# power.net
KiCad netlist of a schematic drawn in Altium Designer
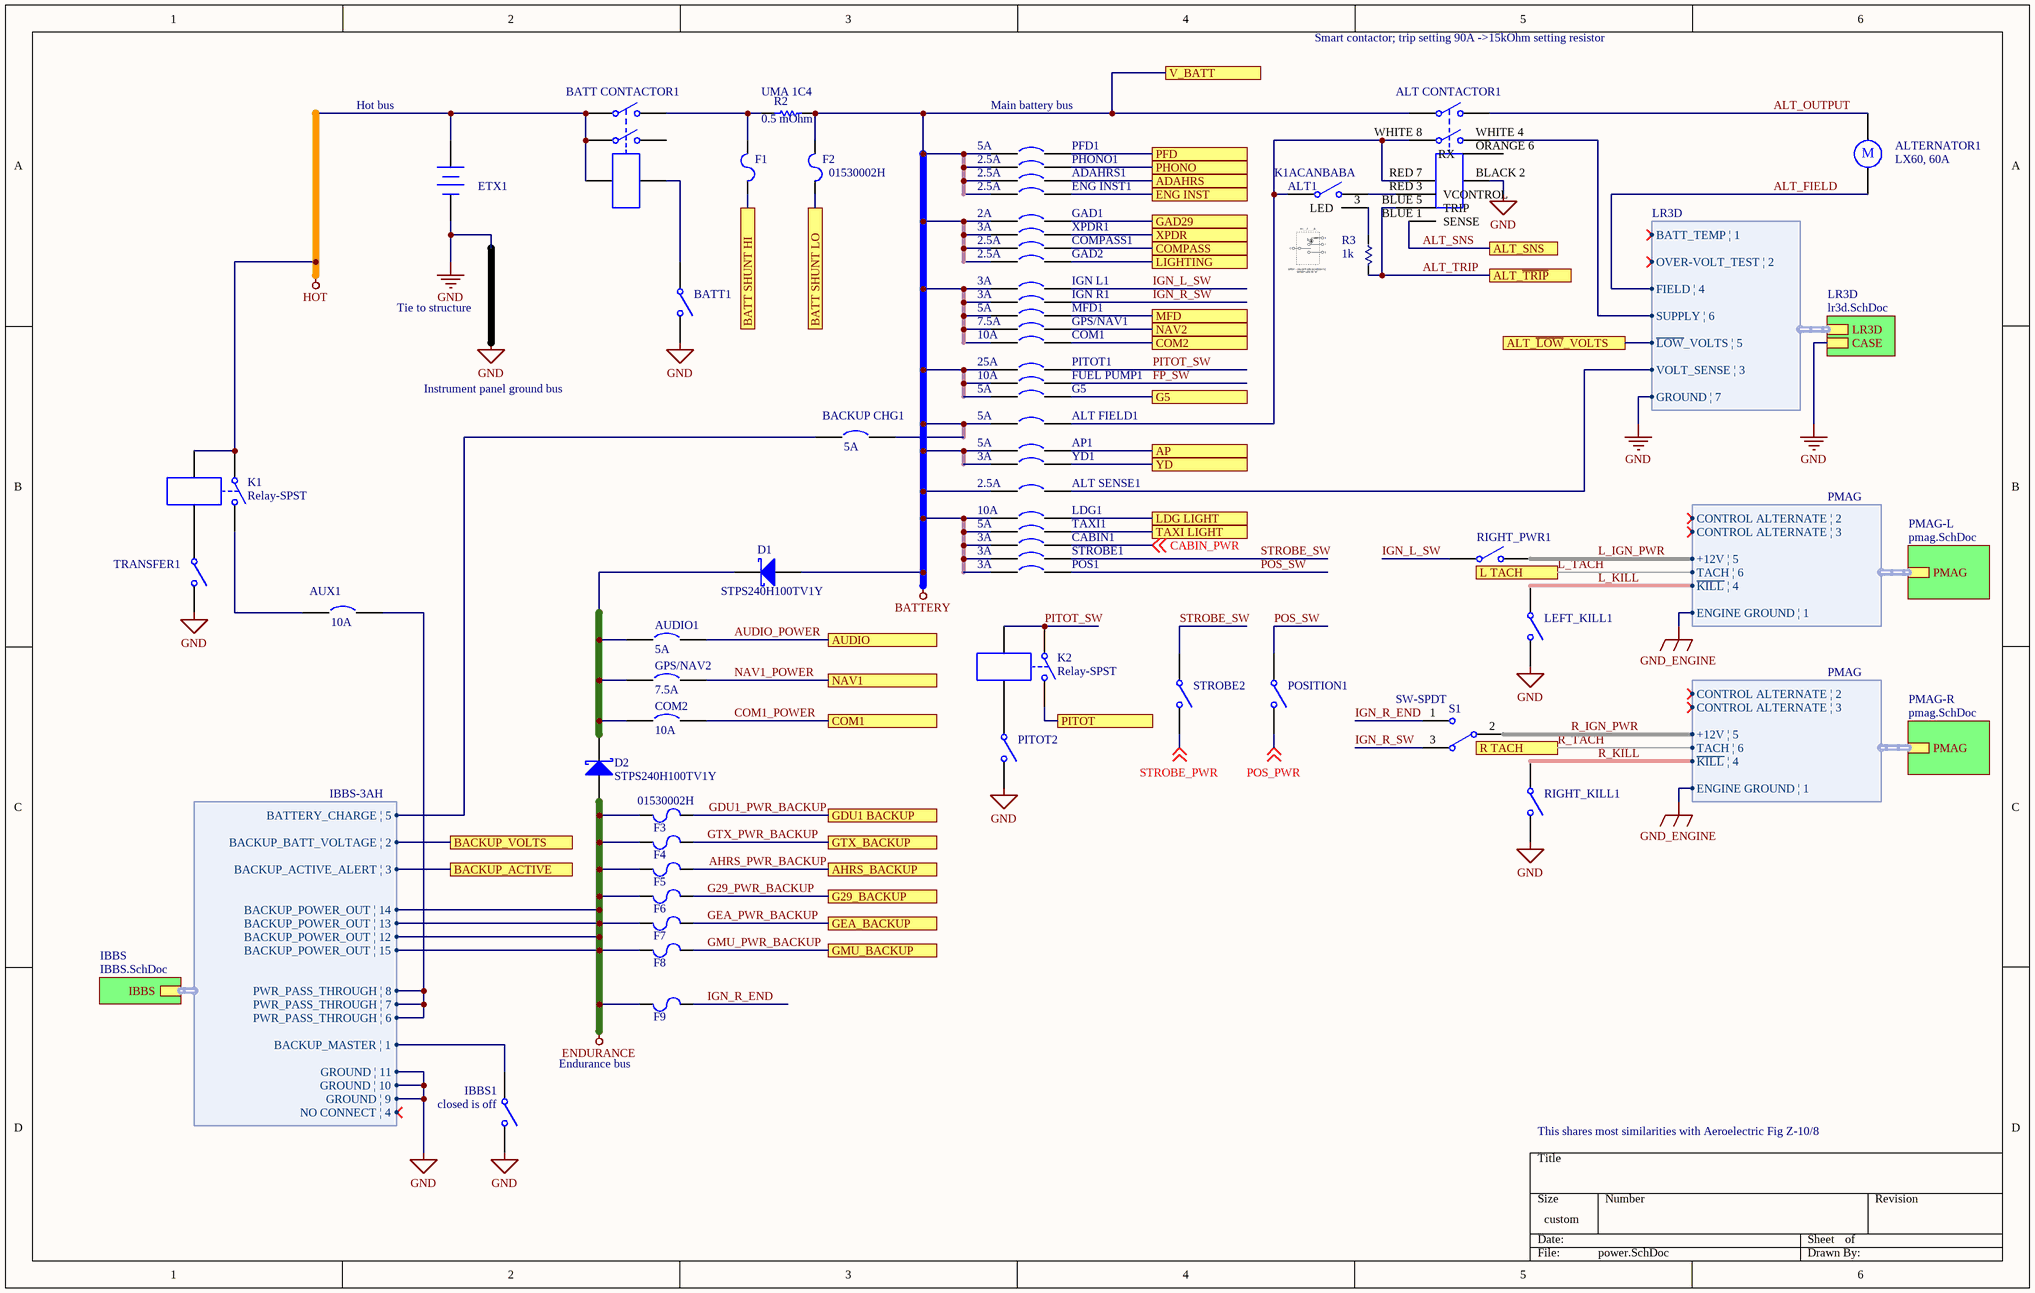
[diagram p0: power.SchDoc]

(export (version "E")
  (design (tool "Eeschema 10.0.6"))
  (components
    (comp (ref "ADAHRS1")
      (value "2.5A")
      (footprint "SPST-2")
      (description "Circuit Breaker")
      (fields (field (name "PUBLISHER") "Altium Limited"))
      (libsource (lib "Miscellaneous Devices") (part "Circuit Breaker"))
    )
    (comp (ref "ALT CONTACTOR1")
      (value "Smart contactor; trip setting 90A ->15kOhm setting resistor")
      (footprint "MODULE6")
      (description "Dual-Pole Single-Throw Relay")
      (fields (field (name "PUBLISHER") "Altium Limited"))
      (libsource (lib "") (part "Relay-DPST_1"))
    )
    (comp (ref "ALT FIELD1")
      (value "5A")
      (footprint "SPST-2")
      (description "Circuit Breaker")
      (fields (field (name "PUBLISHER") "Altium Limited"))
      (libsource (lib "Miscellaneous Devices") (part "Circuit Breaker"))
    )
    (comp (ref "ALT SENSE1")
      (value "2.5A")
      (footprint "SPST-2")
      (description "Circuit Breaker")
      (fields (field (name "PUBLISHER") "Altium Limited"))
      (libsource (lib "Miscellaneous Devices") (part "Circuit Breaker"))
    )
    (comp (ref "ALT1")
      (value "SW-SPST")
      (footprint "SPST-2")
      (description "Single-Pole, Single-Throw Switch")
      (fields (field (name "PUBLISHER") "Altium Limited"))
      (libsource (lib "") (part "SW-SPST_1"))
    )
    (comp (ref "ALTERNATOR1")
      (value "LX60, 60A")
      (footprint "RB5-10.5")
      (description "Motor, General Kind")
      (fields (field (name "PUBLISHER") "Altium Limited"))
      (libsource (lib "Miscellaneous Devices") (part "Motor"))
    )
    (comp (ref "AP1")
      (value "5A")
      (footprint "SPST-2")
      (description "Circuit Breaker")
      (fields (field (name "PUBLISHER") "Altium Limited"))
      (libsource (lib "Miscellaneous Devices") (part "Circuit Breaker"))
    )
    (comp (ref "AUDIO1")
      (value "5A")
      (footprint "SPST-2")
      (description "Circuit Breaker")
      (fields (field (name "PUBLISHER") "Altium Limited"))
      (libsource (lib "Miscellaneous Devices") (part "Circuit Breaker"))
    )
    (comp (ref "AUX1")
      (value "10A")
      (footprint "SPST-2")
      (description "Circuit Breaker")
      (fields (field (name "PUBLISHER") "Altium Limited"))
      (libsource (lib "Miscellaneous Devices") (part "Circuit Breaker"))
    )
    (comp (ref "BACKUP CHG1")
      (value "5A")
      (footprint "SPST-2")
      (description "Circuit Breaker")
      (fields (field (name "PUBLISHER") "Altium Limited"))
      (libsource (lib "Miscellaneous Devices") (part "Circuit Breaker"))
    )
    (comp (ref "BATT CONTACTOR1")
      (value "Relay-DPST")
      (footprint "MODULE6")
      (description "Dual-Pole Single-Throw Relay")
      (fields (field (name "PUBLISHER") "Altium Limited"))
      (libsource (lib "Miscellaneous Devices") (part "Relay-DPST"))
    )
    (comp (ref "BATT1")
      (value "SW-SPST")
      (footprint "SPST-2")
      (description "Single-Pole, Single-Throw Switch")
      (fields (field (name "PUBLISHER") "Altium Limited"))
      (libsource (lib "Miscellaneous Devices") (part "SW-SPST"))
    )
    (comp (ref "CABIN1")
      (value "3A")
      (footprint "SPST-2")
      (description "Circuit Breaker")
      (fields (field (name "PUBLISHER") "Altium Limited"))
      (libsource (lib "Miscellaneous Devices") (part "Circuit Breaker"))
    )
    (comp (ref "COM1")
      (value "10A")
      (footprint "SPST-2")
      (description "Circuit Breaker")
      (fields (field (name "PUBLISHER") "Altium Limited"))
      (libsource (lib "Miscellaneous Devices") (part "Circuit Breaker"))
    )
    (comp (ref "COM2")
      (value "10A")
      (footprint "SPST-2")
      (description "Circuit Breaker")
      (fields (field (name "PUBLISHER") "Altium Limited"))
      (libsource (lib "Miscellaneous Devices") (part "Circuit Breaker"))
    )
    (comp (ref "COMPASS1")
      (value "2.5A")
      (footprint "SPST-2")
      (description "Circuit Breaker")
      (fields (field (name "PUBLISHER") "Altium Limited"))
      (libsource (lib "Miscellaneous Devices") (part "Circuit Breaker"))
    )
    (comp (ref "D1")
      (value "STPS240H100TV1Y")
      (footprint "TO-220AC")
      (description "Schottky Rectifier")
      (fields (field (name "PUBLISHER") "Altium Limited"))
      (libsource (lib "Miscellaneous Devices") (part "Diode 10TQ035"))
    )
    (comp (ref "D2")
      (value "STPS240H100TV1Y")
      (footprint "TO-220AC")
      (description "Schottky Rectifier")
      (fields (field (name "PUBLISHER") "Altium Limited"))
      (libsource (lib "Miscellaneous Devices") (part "Diode 10TQ035"))
    )
    (comp (ref "ENG INST1")
      (value "2.5A")
      (footprint "SPST-2")
      (description "Circuit Breaker")
      (fields (field (name "PUBLISHER") "Altium Limited"))
      (libsource (lib "Miscellaneous Devices") (part "Circuit Breaker"))
    )
    (comp (ref "ETX1")
      (value "Battery")
      (footprint "BAT-2")
      (description "Multicell Battery")
      (fields (field (name "PUBLISHER") "Altium Limited"))
      (libsource (lib "Miscellaneous Devices") (part "Battery"))
    )
    (comp (ref "F1") (value "Fuse") (libsource (lib "component-lib") (part "Fuse")))
    (comp (ref "F2") (value "01530002H") (libsource (lib "component-lib") (part "Fuse")))
    (comp (ref "F3") (value "01530002H") (libsource (lib "component-lib") (part "Fuse")))
    (comp (ref "F4") (value "Fuse") (libsource (lib "component-lib") (part "Fuse")))
    (comp (ref "F5") (value "Fuse") (libsource (lib "component-lib") (part "Fuse")))
    (comp (ref "F6") (value "Fuse") (libsource (lib "component-lib") (part "Fuse")))
    (comp (ref "F7") (value "Fuse") (libsource (lib "component-lib") (part "Fuse")))
    (comp (ref "F8") (value "Fuse") (libsource (lib "component-lib") (part "Fuse")))
    (comp (ref "F9") (value "Fuse") (libsource (lib "component-lib") (part "Fuse")))
    (comp (ref "FUEL PUMP1")
      (value "10A")
      (footprint "SPST-2")
      (description "Circuit Breaker")
      (fields (field (name "PUBLISHER") "Altium Limited"))
      (libsource (lib "Miscellaneous Devices") (part "Circuit Breaker"))
    )
    (comp (ref "G5")
      (value "5A")
      (footprint "SPST-2")
      (description "Circuit Breaker")
      (fields (field (name "PUBLISHER") "Altium Limited"))
      (libsource (lib "Miscellaneous Devices") (part "Circuit Breaker"))
    )
    (comp (ref "GAD1")
      (value "2A")
      (footprint "SPST-2")
      (description "Circuit Breaker")
      (fields (field (name "PUBLISHER") "Altium Limited"))
      (libsource (lib "Miscellaneous Devices") (part "Circuit Breaker"))
    )
    (comp (ref "GAD2")
      (value "2.5A")
      (footprint "SPST-2")
      (description "Circuit Breaker")
      (fields (field (name "PUBLISHER") "Altium Limited"))
      (libsource (lib "Miscellaneous Devices") (part "Circuit Breaker"))
    )
    (comp (ref "GPS/NAV1")
      (value "7.5A")
      (footprint "SPST-2")
      (description "Circuit Breaker")
      (fields (field (name "PUBLISHER") "Altium Limited"))
      (libsource (lib "Miscellaneous Devices") (part "Circuit Breaker"))
    )
    (comp (ref "GPS/NAV2")
      (value "7.5A")
      (footprint "SPST-2")
      (description "Circuit Breaker")
      (fields (field (name "PUBLISHER") "Altium Limited"))
      (libsource (lib "Miscellaneous Devices") (part "Circuit Breaker"))
    )
    (comp (ref "IBBS1")
      (value "SW-SPST")
      (footprint "SPST-2")
      (description "Single-Pole, Single-Throw Switch")
      (fields (field (name "PUBLISHER") "Altium Limited"))
      (libsource (lib "Miscellaneous Devices") (part "SW-SPST"))
    )
    (comp (ref "IGN L1")
      (value "3A")
      (footprint "SPST-2")
      (description "Circuit Breaker")
      (fields (field (name "PUBLISHER") "Altium Limited"))
      (libsource (lib "Miscellaneous Devices") (part "Circuit Breaker"))
    )
    (comp (ref "IGN R1")
      (value "3A")
      (footprint "SPST-2")
      (description "Circuit Breaker")
      (fields (field (name "PUBLISHER") "Altium Limited"))
      (libsource (lib "Miscellaneous Devices") (part "Circuit Breaker"))
    )
    (comp (ref "K1")
      (value "Relay-SPST")
      (footprint "MODULE4")
      (description "Single-Pole Single-Throw Relay")
      (fields (field (name "PUBLISHER") "Altium Limited"))
      (libsource (lib "Miscellaneous Devices") (part "Relay-SPST"))
    )
    (comp (ref "K2")
      (value "Relay-SPST")
      (footprint "MODULE4")
      (description "Single-Pole Single-Throw Relay")
      (fields (field (name "PUBLISHER") "Altium Limited"))
      (libsource (lib "Miscellaneous Devices") (part "Relay-SPST"))
    )
    (comp (ref "LDG1")
      (value "10A")
      (footprint "SPST-2")
      (description "Circuit Breaker")
      (fields (field (name "PUBLISHER") "Altium Limited"))
      (libsource (lib "Miscellaneous Devices") (part "Circuit Breaker"))
    )
    (comp (ref "LEFT_KILL1")
      (value "SW-SPST")
      (footprint "SPST-2")
      (description "Single-Pole, Single-Throw Switch")
      (fields (field (name "PUBLISHER") "Altium Limited"))
      (libsource (lib "Miscellaneous Devices") (part "SW-SPST"))
    )
    (comp (ref "MFD1")
      (value "5A")
      (footprint "SPST-2")
      (description "Circuit Breaker")
      (fields (field (name "PUBLISHER") "Altium Limited"))
      (libsource (lib "Miscellaneous Devices") (part "Circuit Breaker"))
    )
    (comp (ref "PFD1")
      (value "5A")
      (footprint "SPST-2")
      (description "Circuit Breaker")
      (fields (field (name "PUBLISHER") "Altium Limited"))
      (libsource (lib "Miscellaneous Devices") (part "Circuit Breaker"))
    )
    (comp (ref "PHONO1")
      (value "2.5A")
      (footprint "SPST-2")
      (description "Circuit Breaker")
      (fields (field (name "PUBLISHER") "Altium Limited"))
      (libsource (lib "Miscellaneous Devices") (part "Circuit Breaker"))
    )
    (comp (ref "PITOT1")
      (value "25A")
      (footprint "SPST-2")
      (description "Circuit Breaker")
      (fields (field (name "PUBLISHER") "Altium Limited"))
      (libsource (lib "Miscellaneous Devices") (part "Circuit Breaker"))
    )
    (comp (ref "PITOT2")
      (value "SW-SPST")
      (footprint "SPST-2")
      (description "Single-Pole, Single-Throw Switch")
      (fields (field (name "PUBLISHER") "Altium Limited"))
      (libsource (lib "Miscellaneous Devices") (part "SW-SPST"))
    )
    (comp (ref "POS1")
      (value "3A")
      (footprint "SPST-2")
      (description "Circuit Breaker")
      (fields (field (name "PUBLISHER") "Altium Limited"))
      (libsource (lib "Miscellaneous Devices") (part "Circuit Breaker"))
    )
    (comp (ref "POSITION1")
      (value "SW-SPST")
      (footprint "SPST-2")
      (description "Single-Pole, Single-Throw Switch")
      (fields (field (name "PUBLISHER") "Altium Limited"))
      (libsource (lib "Miscellaneous Devices") (part "SW-SPST"))
    )
    (comp (ref "R2")
      (value "UMA 1C4")
      (footprint "AXIAL-0.3")
      (description "Resistor")
      (fields (field (name "ALTIUM_VALUE") "0.5 mOhm") (field (name "PUBLISHER") "Altium Limited"))
      (libsource (lib "Miscellaneous Devices") (part "Res1"))
    )
    (comp (ref "R3")
      (value "RN60D1001FRE6")
      (footprint "RESC1608L")
      (fields (field (name "TOLERANCE") "±5%") (field (name "RESISTANCE (OHMS)") "1k"))
      (libsource (lib "resistor") (part "RES_470-0603"))
    )
    (comp (ref "RIGHT_KILL1")
      (value "SW-SPST")
      (footprint "SPST-2")
      (description "Single-Pole, Single-Throw Switch")
      (fields (field (name "PUBLISHER") "Altium Limited"))
      (libsource (lib "Miscellaneous Devices") (part "SW-SPST"))
    )
    (comp (ref "RIGHT_PWR1")
      (value "SW-SPST")
      (footprint "SPST-2")
      (description "Single-Pole, Single-Throw Switch")
      (fields (field (name "PUBLISHER") "Altium Limited"))
      (libsource (lib "Miscellaneous Devices") (part "SW-SPST"))
    )
    (comp (ref "S1")
      (value "SW-SPDT")
      (footprint "TL36WW15050")
      (description "SPDT Subminiature Toggle Switch, Right Angle Mounting, Vertical Actuation")
      (fields (field (name "PUBLISHER") "Altium Limited"))
      (libsource (lib "Miscellaneous Devices") (part "SW-SPDT"))
    )
    (comp (ref "STROBE1")
      (value "3A")
      (footprint "SPST-2")
      (description "Circuit Breaker")
      (fields (field (name "PUBLISHER") "Altium Limited"))
      (libsource (lib "Miscellaneous Devices") (part "Circuit Breaker"))
    )
    (comp (ref "STROBE2")
      (value "SW-SPST")
      (footprint "SPST-2")
      (description "Single-Pole, Single-Throw Switch")
      (fields (field (name "PUBLISHER") "Altium Limited"))
      (libsource (lib "Miscellaneous Devices") (part "SW-SPST"))
    )
    (comp (ref "TAXI1")
      (value "5A")
      (footprint "SPST-2")
      (description "Circuit Breaker")
      (fields (field (name "PUBLISHER") "Altium Limited"))
      (libsource (lib "Miscellaneous Devices") (part "Circuit Breaker"))
    )
    (comp (ref "TRANSFER1")
      (value "SW-SPST")
      (footprint "SPST-2")
      (description "Single-Pole, Single-Throw Switch")
      (fields (field (name "PUBLISHER") "Altium Limited"))
      (libsource (lib "Miscellaneous Devices") (part "SW-SPST"))
    )
    (comp (ref "XPDR1")
      (value "3A")
      (footprint "SPST-2")
      (description "Circuit Breaker")
      (fields (field (name "PUBLISHER") "Altium Limited"))
      (libsource (lib "Miscellaneous Devices") (part "Circuit Breaker"))
    )
    (comp (ref "YD1")
      (value "3A")
      (footprint "SPST-2")
      (description "Circuit Breaker")
      (fields (field (name "PUBLISHER") "Altium Limited"))
      (libsource (lib "Miscellaneous Devices") (part "Circuit Breaker"))
    )
  )
  (nets
    (net (code "4") (name "/ADAHRS") (class "Default")
      (node (ref "ADAHRS1") (pin "2") (pinfunction "2_2") (pintype "passive"))
    )
    (net (code "5") (name "/AHRS_PWR_BACKUP") (class "Default")
      (node (ref "F5") (pin "14") (pinfunction "14_14") (pintype "passive"))
    )
    (net (code "6") (name "/ALT_FIELD") (class "Default")
      (node (ref "ALTERNATOR1") (pin "2") (pinfunction "2_2") (pintype "passive"))
    )
    (net (code "7") (name "/ALT_OUTPUT") (class "Default")
      (node (ref "ALT CONTACTOR1") (pin "2") (pinfunction "2_2") (pintype "passive"))
      (node (ref "ALTERNATOR1") (pin "1") (pinfunction "1_1") (pintype "passive"))
    )
    (net (code "8") (name "/ALT_SNS") (class "Default")
      (node (ref "ALT CONTACTOR1") (pin "BLUE_1") (pinfunction "SENSE_BLUE_1") (pintype "passive"))
    )
    (net (code "9") (name "/ALT_TRIP") (class "Default")
      (node (ref "ALT CONTACTOR1") (pin "BLUE_5") (pinfunction "TRIP_BLUE_5") (pintype "passive"))
      (node (ref "R3") (pin "2") (pintype "passive"))
    )
    (net (code "11") (name "/AP") (class "Default")
      (node (ref "AP1") (pin "2") (pinfunction "2_2") (pintype "passive"))
    )
    (net (code "12") (name "/AUDIO_POWER") (class "Default")
      (node (ref "AUDIO1") (pin "2") (pinfunction "2_2") (pintype "passive"))
    )
    (net (code "14") (name "/BACKUP_MASTER ¦ 1") (class "Default")
      (node (ref "IBBS1") (pin "1") (pinfunction "COMMON_1") (pintype "passive"))
    )
    (net (code "16") (name "/BATT SHUNT HI") (class "Default")
      (node (ref "F1") (pin "14") (pinfunction "14_14") (pintype "passive"))
    )
    (net (code "17") (name "/BATT SHUNT LO") (class "Default")
      (node (ref "F2") (pin "14") (pinfunction "14_14") (pintype "passive"))
    )
    (net (code "18") (name "/BATTERY_CHARGE ¦ 5") (class "Default")
      (node (ref "BACKUP CHG1") (pin "1") (pinfunction "1_1") (pintype "passive"))
    )
    (net (code "19") (name "/COM1_POWER") (class "Default")
      (node (ref "COM2") (pin "2") (pinfunction "2_2") (pintype "passive"))
    )
    (net (code "20") (name "/COM2") (class "Default")
      (node (ref "COM1") (pin "2") (pinfunction "2_2") (pintype "passive"))
    )
    (net (code "21") (name "/COMPASS") (class "Default")
      (node (ref "COMPASS1") (pin "2") (pinfunction "2_2") (pintype "passive"))
    )
    (net (code "22") (name "/ENG INST") (class "Default")
      (node (ref "ENG INST1") (pin "2") (pinfunction "2_2") (pintype "passive"))
    )
    (net (code "23") (name "/FP_SW") (class "Default")
      (node (ref "FUEL PUMP1") (pin "2") (pinfunction "2_2") (pintype "passive"))
    )
    (net (code "24") (name "/G5") (class "Default")
      (node (ref "G5") (pin "2") (pinfunction "2_2") (pintype "passive"))
    )
    (net (code "25") (name "/G29_PWR_BACKUP") (class "Default")
      (node (ref "F6") (pin "14") (pinfunction "14_14") (pintype "passive"))
    )
    (net (code "26") (name "/GAD29") (class "Default")
      (node (ref "GAD1") (pin "2") (pinfunction "2_2") (pintype "passive"))
    )
    (net (code "27") (name "/GDU1_PWR_BACKUP") (class "Default")
      (node (ref "F3") (pin "14") (pinfunction "14_14") (pintype "passive"))
    )
    (net (code "28") (name "/GEA_PWR_BACKUP") (class "Default")
      (node (ref "F7") (pin "14") (pinfunction "14_14") (pintype "passive"))
    )
    (net (code "29") (name "/GMU_PWR_BACKUP") (class "Default")
      (node (ref "F8") (pin "14") (pinfunction "14_14") (pintype "passive"))
    )
    (net (code "30") (name "/GTX_PWR_BACKUP") (class "Default")
      (node (ref "F4") (pin "14") (pinfunction "14_14") (pintype "passive"))
    )
    (net (code "31") (name "/IGN_L_SW") (class "Default")
      (node (ref "IGN L1") (pin "2") (pinfunction "2_2") (pintype "passive"))
      (node (ref "RIGHT_PWR1") (pin "1") (pinfunction "COMMON_1") (pintype "passive"))
    )
    (net (code "32") (name "/IGN_R_END") (class "Default")
      (node (ref "F9") (pin "14") (pinfunction "14_14") (pintype "passive"))
      (node (ref "S1") (pin "1") (pinfunction "1_1") (pintype "passive"))
    )
    (net (code "33") (name "/IGN_R_SW") (class "Default")
      (node (ref "IGN R1") (pin "2") (pinfunction "2_2") (pintype "passive"))
      (node (ref "S1") (pin "3") (pinfunction "3_3") (pintype "passive"))
    )
    (net (code "34") (name "/LDG LIGHT") (class "Default")
      (node (ref "LDG1") (pin "2") (pinfunction "2_2") (pintype "passive"))
    )
    (net (code "35") (name "/LIGHTING") (class "Default")
      (node (ref "GAD2") (pin "2") (pinfunction "2_2") (pintype "passive"))
    )
    (net (code "36") (name "/L_IGN_PWR") (class "Default")
      (node (ref "RIGHT_PWR1") (pin "2") (pinfunction "NO_2") (pintype "passive"))
    )
    (net (code "38") (name "/L_~{KILL}") (class "Default")
      (node (ref "LEFT_KILL1") (pin "1") (pinfunction "COMMON_1") (pintype "passive"))
    )
    (net (code "39") (name "/MFD") (class "Default")
      (node (ref "MFD1") (pin "2") (pinfunction "2_2") (pintype "passive"))
    )
    (net (code "40") (name "/NAV1_POWER") (class "Default")
      (node (ref "GPS/NAV2") (pin "2") (pinfunction "2_2") (pintype "passive"))
    )
    (net (code "41") (name "/NAV2") (class "Default")
      (node (ref "GPS/NAV1") (pin "2") (pinfunction "2_2") (pintype "passive"))
    )
    (net (code "42") (name "/PFD") (class "Default")
      (node (ref "PFD1") (pin "2") (pinfunction "2_2") (pintype "passive"))
    )
    (net (code "43") (name "/PHONO") (class "Default")
      (node (ref "PHONO1") (pin "2") (pinfunction "2_2") (pintype "passive"))
    )
    (net (code "44") (name "/PITOT") (class "Default")
      (node (ref "K2") (pin "2") (pinfunction "2_2") (pintype "passive"))
    )
    (net (code "45") (name "/PITOT_SW") (class "Default")
      (node (ref "K2") (pin "1") (pinfunction "1_1") (pintype "passive"))
      (node (ref "K2") (pin "3") (pinfunction "3_3") (pintype "passive"))
      (node (ref "PITOT1") (pin "2") (pinfunction "2_2") (pintype "passive"))
    )
    (net (code "46") (name "/POS_SW") (class "Default")
      (node (ref "POS1") (pin "2") (pinfunction "2_2") (pintype "passive"))
      (node (ref "POSITION1") (pin "1") (pinfunction "COMMON_1") (pintype "passive"))
    )
    (net (code "47") (name "/PWR_PASS_THROUGH ¦ 6") (class "Default")
      (node (ref "AUX1") (pin "2") (pinfunction "2_2") (pintype "passive"))
    )
    (net (code "48") (name "/R_IGN_PWR") (class "Default")
      (node (ref "S1") (pin "2") (pinfunction "2_2") (pintype "passive"))
    )
    (net (code "50") (name "/R_~{KILL}") (class "Default")
      (node (ref "RIGHT_KILL1") (pin "1") (pinfunction "COMMON_1") (pintype "passive"))
    )
    (net (code "51") (name "/STROBE_SW") (class "Default")
      (node (ref "STROBE1") (pin "2") (pinfunction "2_2") (pintype "passive"))
      (node (ref "STROBE2") (pin "1") (pinfunction "COMMON_1") (pintype "passive"))
    )
    (net (code "52") (name "/SUPPLY ¦ 6") (class "Default")
      (node (ref "ALT CONTACTOR1") (pin "WHITE_4") (pinfunction "4_WHITE_4") (pintype "passive"))
    )
    (net (code "53") (name "/TAXI LIGHT") (class "Default")
      (node (ref "TAXI1") (pin "2") (pinfunction "2_2") (pintype "passive"))
    )
    (net (code "54") (name "/VOLT_SENSE ¦ 3") (class "Default")
      (node (ref "ALT SENSE1") (pin "2") (pinfunction "2_2") (pintype "passive"))
    )
    (net (code "55") (name "/XPDR") (class "Default")
      (node (ref "XPDR1") (pin "2") (pinfunction "2_2") (pintype "passive"))
    )
    (net (code "56") (name "/YD") (class "Default")
      (node (ref "YD1") (pin "2") (pinfunction "2_2") (pintype "passive"))
    )
    (net (code "60") (name "BATTERY") (class "Default")
      (node (ref "ADAHRS1") (pin "1") (pinfunction "1_1") (pintype "passive"))
      (node (ref "ALT CONTACTOR1") (pin "1") (pinfunction "1_1") (pintype "passive"))
      (node (ref "ALT FIELD1") (pin "1") (pinfunction "1_1") (pintype "passive"))
      (node (ref "ALT SENSE1") (pin "1") (pinfunction "1_1") (pintype "passive"))
      (node (ref "AP1") (pin "1") (pinfunction "1_1") (pintype "passive"))
      (node (ref "BACKUP CHG1") (pin "2") (pinfunction "2_2") (pintype "passive"))
      (node (ref "CABIN1") (pin "1") (pinfunction "1_1") (pintype "passive"))
      (node (ref "COM1") (pin "1") (pinfunction "1_1") (pintype "passive"))
      (node (ref "COMPASS1") (pin "1") (pinfunction "1_1") (pintype "passive"))
      (node (ref "D1") (pin "3") (pinfunction "A_3") (pintype "passive"))
      (node (ref "ENG INST1") (pin "1") (pinfunction "1_1") (pintype "passive"))
      (node (ref "F2") (pin "13") (pinfunction "13_13") (pintype "passive"))
      (node (ref "FUEL PUMP1") (pin "1") (pinfunction "1_1") (pintype "passive"))
      (node (ref "G5") (pin "1") (pinfunction "1_1") (pintype "passive"))
      (node (ref "GAD1") (pin "1") (pinfunction "1_1") (pintype "passive"))
      (node (ref "GAD2") (pin "1") (pinfunction "1_1") (pintype "passive"))
      (node (ref "GPS/NAV1") (pin "1") (pinfunction "1_1") (pintype "passive"))
      (node (ref "IGN L1") (pin "1") (pinfunction "1_1") (pintype "passive"))
      (node (ref "IGN R1") (pin "1") (pinfunction "1_1") (pintype "passive"))
      (node (ref "LDG1") (pin "1") (pinfunction "1_1") (pintype "passive"))
      (node (ref "MFD1") (pin "1") (pinfunction "1_1") (pintype "passive"))
      (node (ref "PFD1") (pin "1") (pinfunction "1_1") (pintype "passive"))
      (node (ref "PHONO1") (pin "1") (pinfunction "1_1") (pintype "passive"))
      (node (ref "PITOT1") (pin "1") (pinfunction "1_1") (pintype "passive"))
      (node (ref "POS1") (pin "1") (pinfunction "1_1") (pintype "passive"))
      (node (ref "R2") (pin "2") (pinfunction "2_2") (pintype "passive"))
      (node (ref "STROBE1") (pin "1") (pinfunction "1_1") (pintype "passive"))
      (node (ref "TAXI1") (pin "1") (pinfunction "1_1") (pintype "passive"))
      (node (ref "XPDR1") (pin "1") (pinfunction "1_1") (pintype "passive"))
      (node (ref "YD1") (pin "1") (pinfunction "1_1") (pintype "passive"))
    )
    (net (code "61") (name "CABIN_PWR") (class "Default")
      (node (ref "CABIN1") (pin "2") (pinfunction "2_2") (pintype "passive"))
    )
    (net (code "62") (name "ENDURANCE") (class "Default")
      (node (ref "D2") (pin "3") (pinfunction "A_3") (pintype "passive"))
      (node (ref "F3") (pin "13") (pinfunction "13_13") (pintype "passive"))
      (node (ref "F4") (pin "13") (pinfunction "13_13") (pintype "passive"))
      (node (ref "F5") (pin "13") (pinfunction "13_13") (pintype "passive"))
      (node (ref "F6") (pin "13") (pinfunction "13_13") (pintype "passive"))
      (node (ref "F7") (pin "13") (pinfunction "13_13") (pintype "passive"))
      (node (ref "F8") (pin "13") (pinfunction "13_13") (pintype "passive"))
      (node (ref "F9") (pin "13") (pinfunction "13_13") (pintype "passive"))
    )
    (net (code "63") (name "GND") (class "Default")
      (node (ref "ALT CONTACTOR1") (pin "BLACK_2") (pinfunction "6_BLACK_2") (pintype "passive"))
      (node (ref "BATT1") (pin "2") (pinfunction "NO_2") (pintype "passive"))
      (node (ref "ETX1") (pin "2") (pinfunction "-_2") (pintype "passive"))
      (node (ref "IBBS1") (pin "2") (pinfunction "NO_2") (pintype "passive"))
      (node (ref "LEFT_KILL1") (pin "2") (pinfunction "NO_2") (pintype "passive"))
      (node (ref "PITOT2") (pin "2") (pinfunction "NO_2") (pintype "passive"))
      (node (ref "RIGHT_KILL1") (pin "2") (pinfunction "NO_2") (pintype "passive"))
      (node (ref "TRANSFER1") (pin "2") (pinfunction "NO_2") (pintype "passive"))
    )
    (net (code "65") (name "HOT") (class "Default")
      (node (ref "BATT CONTACTOR1") (pin "1") (pinfunction "1_1") (pintype "passive"))
      (node (ref "BATT CONTACTOR1") (pin "3") (pinfunction "3_3") (pintype "passive"))
      (node (ref "BATT CONTACTOR1") (pin "5") (pinfunction "5_5") (pintype "passive"))
      (node (ref "ETX1") (pin "1") (pinfunction "+_1") (pintype "passive"))
      (node (ref "K1") (pin "1") (pinfunction "1_1") (pintype "passive"))
      (node (ref "K1") (pin "3") (pinfunction "3_3") (pintype "passive"))
    )
    (net (code "66") (name "Net-(ALT CONTACTOR1-3)") (class "Default")
      (node (ref "ALT CONTACTOR1") (pin "RED_7") (pinfunction "5_RED_7") (pintype "passive"))
      (node (ref "ALT CONTACTOR1") (pin "WHITE_8") (pinfunction "3_WHITE_8") (pintype "passive"))
      (node (ref "ALT FIELD1") (pin "2") (pinfunction "2_2") (pintype "passive"))
      (node (ref "ALT1") (pin "C") (pinfunction "C_C") (pintype "passive"))
    )
    (net (code "67") (name "Net-(ALT CONTACTOR1-VCONTROL)") (class "Default")
      (node (ref "ALT CONTACTOR1") (pin "RED_3") (pinfunction "VCONTROL_RED_3") (pintype "passive"))
      (node (ref "ALT1") (pin "1") (pinfunction "NO_1") (pintype "passive"))
    )
    (net (code "68") (name "Net-(ALT1-LED)") (class "Default")
      (node (ref "ALT1") (pin "3") (pinfunction "LED_3") (pintype "passive"))
      (node (ref "R3") (pin "1") (pintype "passive"))
    )
    (net (code "69") (name "Net-(AUX1-Pad1)") (class "Default")
      (node (ref "AUX1") (pin "1") (pinfunction "1_1") (pintype "passive"))
      (node (ref "K1") (pin "2") (pinfunction "2_2") (pintype "passive"))
    )
    (net (code "70") (name "Net-(BATT CONTACTOR1-Pad2)") (class "Default")
      (node (ref "BATT CONTACTOR1") (pin "2") (pinfunction "2_2") (pintype "passive"))
      (node (ref "F1") (pin "13") (pinfunction "13_13") (pintype "passive"))
      (node (ref "R2") (pin "1") (pinfunction "1_1") (pintype "passive"))
    )
    (net (code "71") (name "Net-(BATT1-COMMON)") (class "Default")
      (node (ref "BATT CONTACTOR1") (pin "6") (pinfunction "6_6") (pintype "passive"))
      (node (ref "BATT1") (pin "1") (pinfunction "COMMON_1") (pintype "passive"))
    )
    (net (code "72") (name "Net-(D1-K)") (class "Default")
      (node (ref "AUDIO1") (pin "1") (pinfunction "1_1") (pintype "passive"))
      (node (ref "COM2") (pin "1") (pinfunction "1_1") (pintype "passive"))
      (node (ref "D1") (pin "1") (pinfunction "K_1") (pintype "passive"))
      (node (ref "D2") (pin "1") (pinfunction "K_1") (pintype "passive"))
      (node (ref "GPS/NAV2") (pin "1") (pinfunction "1_1") (pintype "passive"))
    )
    (net (code "73") (name "Net-(PITOT2-COMMON)") (class "Default")
      (node (ref "K2") (pin "4") (pinfunction "4_4") (pintype "passive"))
      (node (ref "PITOT2") (pin "1") (pinfunction "COMMON_1") (pintype "passive"))
    )
    (net (code "74") (name "Net-(TRANSFER1-COMMON)") (class "Default")
      (node (ref "K1") (pin "4") (pinfunction "4_4") (pintype "passive"))
      (node (ref "TRANSFER1") (pin "1") (pinfunction "COMMON_1") (pintype "passive"))
    )
    (net (code "75") (name "POS_PWR") (class "Default")
      (node (ref "POSITION1") (pin "2") (pinfunction "NO_2") (pintype "passive"))
    )
    (net (code "76") (name "STROBE_PWR") (class "Default")
      (node (ref "STROBE2") (pin "2") (pinfunction "NO_2") (pintype "passive"))
    )
    (net (code "77") (name "unconnected-(ALT CONTACTOR1-RX-PadORANGE_6)") (class "Default")
      (node (ref "ALT CONTACTOR1") (pin "ORANGE_6") (pinfunction "RX_ORANGE_6") (pintype "passive"))
    )
    (net (code "78") (name "unconnected-(BATT CONTACTOR1-Pad4)") (class "Default")
      (node (ref "BATT CONTACTOR1") (pin "4") (pinfunction "4_4") (pintype "passive"))
    )
  )
)
